# 20_CLOCKS.net
KiCad netlist of a schematic drawn in Altium Designer
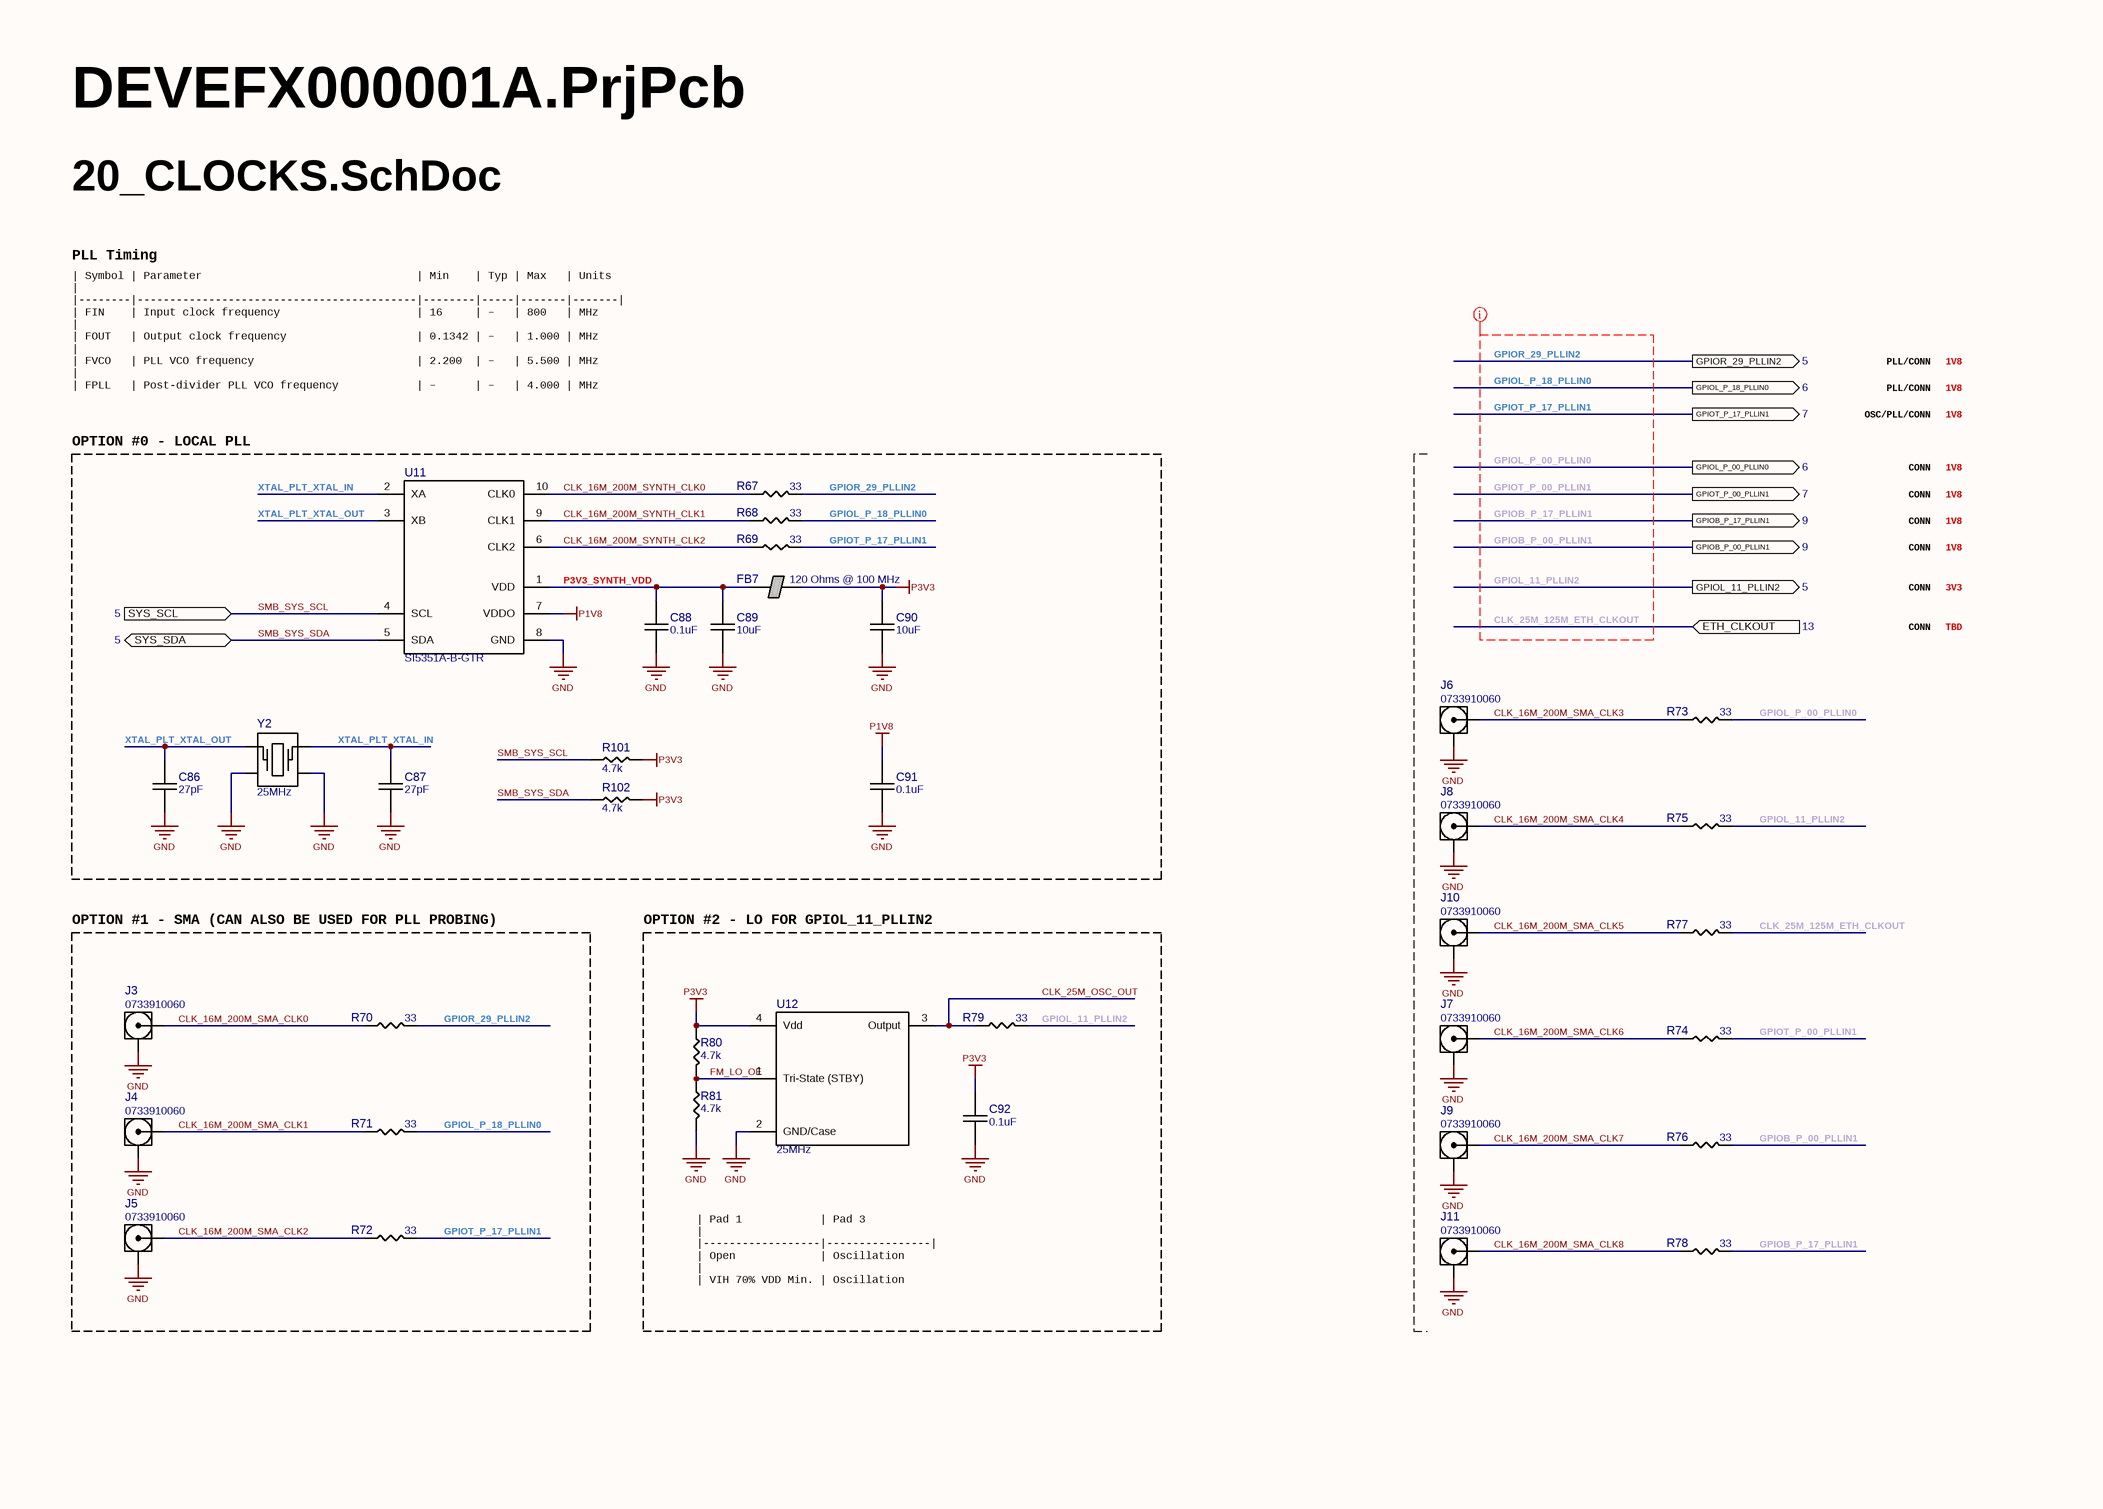
[diagram p0: 20_CLOCKS.SchDoc]

(export (version "E")
  (design (tool "Eeschema 10.0.6"))
  (components
    (comp (ref "C86")
      (value "27pF")
      (footprint "CAPC1005X06N")
      (description "CAP CER 27PF 50V C0G/NPO 0402")
      (fields (field (name "PART NUMBER") "CC0402JRNPO9BN270") (field (name "VOLTAGE") "50V"))
      (libsource (lib "Database") (part "Capacitor"))
    )
    (comp (ref "C87")
      (value "27pF")
      (footprint "CAPC1005X06N")
      (description "CAP CER 27PF 50V C0G/NPO 0402")
      (fields (field (name "PART NUMBER") "CC0402JRNPO9BN270") (field (name "VOLTAGE") "50V"))
      (libsource (lib "Database") (part "Capacitor"))
    )
    (comp (ref "C88")
      (value "0.1uF")
      (footprint "CAPC1005X06N")
      (description "CAP CER 0.1UF 25V X7R 0402")
      (fields (field (name "PART NUMBER") "GRM155R71E104KE14J") (field (name "VOLTAGE") "25V"))
      (libsource (lib "Database") (part "Capacitor"))
    )
    (comp (ref "C89")
      (value "10uF")
      (footprint "CAPC1005X06N")
      (description "CAP CER 10UF 6.3V X5R 0402")
      (fields (field (name "PART NUMBER") "GRM155R60J106ME47D") (field (name "VOLTAGE") "6.3V"))
      (libsource (lib "Database") (part "Capacitor"))
    )
    (comp (ref "C90")
      (value "10uF")
      (footprint "CAPC1005X06N")
      (description "CAP CER 10UF 6.3V X5R 0402")
      (fields (field (name "PART NUMBER") "GRM155R60J106ME47D") (field (name "VOLTAGE") "6.3V"))
      (libsource (lib "Database") (part "Capacitor"))
    )
    (comp (ref "C91")
      (value "0.1uF")
      (footprint "CAPC1005X06N")
      (description "CAP CER 0.1UF 25V X7R 0402")
      (fields (field (name "PART NUMBER") "GRM155R71E104KE14J") (field (name "VOLTAGE") "25V"))
      (libsource (lib "Database") (part "Capacitor"))
    )
    (comp (ref "C92")
      (value "0.1uF")
      (footprint "CAPC1005X06N")
      (description "CAP CER 0.1UF 25V X7R 0402")
      (fields (field (name "PART NUMBER") "GRM155R71E104KE14J") (field (name "VOLTAGE") "25V"))
      (libsource (lib "Database") (part "Capacitor"))
    )
    (comp (ref "FB7")
      (value "120 Ohms @ 100 MHz")
      (footprint "INDC1005X05N")
      (description "FERRITE BEAD 120 OHM 0402 1LN")
      (fields (field (name "PART NUMBER") "BLM15PD121SN1D"))
      (libsource (lib "Database") (part "Bead"))
    )
    (comp (ref "J3")
      (value "0733910060")
      (footprint "MOLEX_0733910060")
      (description "CONN SMA RCPT STR 50 OHM PCB")
      (libsource (lib "Database") (part "Connector RF"))
    )
    (comp (ref "J4")
      (value "0733910060")
      (footprint "MOLEX_0733910060")
      (description "CONN SMA RCPT STR 50 OHM PCB")
      (libsource (lib "Database") (part "Connector RF"))
    )
    (comp (ref "J5")
      (value "0733910060")
      (footprint "MOLEX_0733910060")
      (description "CONN SMA RCPT STR 50 OHM PCB")
      (libsource (lib "Database") (part "Connector RF"))
    )
    (comp (ref "J6")
      (value "0733910060")
      (footprint "MOLEX_0733910060")
      (description "CONN SMA RCPT STR 50 OHM PCB")
      (libsource (lib "Database") (part "Connector RF"))
    )
    (comp (ref "J7")
      (value "0733910060")
      (footprint "MOLEX_0733910060")
      (description "CONN SMA RCPT STR 50 OHM PCB")
      (libsource (lib "Database") (part "Connector RF"))
    )
    (comp (ref "J8")
      (value "0733910060")
      (footprint "MOLEX_0733910060")
      (description "CONN SMA RCPT STR 50 OHM PCB")
      (libsource (lib "Database") (part "Connector RF"))
    )
    (comp (ref "J9")
      (value "0733910060")
      (footprint "MOLEX_0733910060")
      (description "CONN SMA RCPT STR 50 OHM PCB")
      (libsource (lib "Database") (part "Connector RF"))
    )
    (comp (ref "J10")
      (value "0733910060")
      (footprint "MOLEX_0733910060")
      (description "CONN SMA RCPT STR 50 OHM PCB")
      (libsource (lib "Database") (part "Connector RF"))
    )
    (comp (ref "J11")
      (value "0733910060")
      (footprint "MOLEX_0733910060")
      (description "CONN SMA RCPT STR 50 OHM PCB")
      (libsource (lib "Database") (part "Connector RF"))
    )
    (comp (ref "R67")
      (value "33")
      (footprint "RESC1005X03N")
      (description "RES SMD 33 OHM 1% 1/16W 0402")
      (fields (field (name "PART NUMBER") "RC0402FR-0733RL"))
      (libsource (lib "Database") (part "Resistor_ENG"))
    )
    (comp (ref "R68")
      (value "33")
      (footprint "RESC1005X03N")
      (description "RES SMD 33 OHM 1% 1/16W 0402")
      (fields (field (name "PART NUMBER") "RC0402FR-0733RL"))
      (libsource (lib "Database") (part "Resistor_ENG"))
    )
    (comp (ref "R69")
      (value "33")
      (footprint "RESC1005X03N")
      (description "RES SMD 33 OHM 1% 1/16W 0402")
      (fields (field (name "PART NUMBER") "RC0402FR-0733RL"))
      (libsource (lib "Database") (part "Resistor_ENG"))
    )
    (comp (ref "R70")
      (value "33")
      (footprint "RESC1005X03N")
      (description "RES SMD 33 OHM 1% 1/16W 0402")
      (fields (field (name "PART NUMBER") "RC0402FR-0733RL"))
      (libsource (lib "Database") (part "Resistor_ENG"))
    )
    (comp (ref "R71")
      (value "33")
      (footprint "RESC1005X03N")
      (description "RES SMD 33 OHM 1% 1/16W 0402")
      (fields (field (name "PART NUMBER") "RC0402FR-0733RL"))
      (libsource (lib "Database") (part "Resistor_ENG"))
    )
    (comp (ref "R72")
      (value "33")
      (footprint "RESC1005X03N")
      (description "RES SMD 33 OHM 1% 1/16W 0402")
      (fields (field (name "PART NUMBER") "RC0402FR-0733RL"))
      (libsource (lib "Database") (part "Resistor_ENG"))
    )
    (comp (ref "R73")
      (value "33")
      (footprint "RESC1005X03N")
      (description "RES SMD 33 OHM 1% 1/16W 0402")
      (fields (field (name "PART NUMBER") "RC0402FR-0733RL"))
      (libsource (lib "Database") (part "Resistor_ENG"))
    )
    (comp (ref "R74")
      (value "33")
      (footprint "RESC1005X03N")
      (description "RES SMD 33 OHM 1% 1/16W 0402")
      (fields (field (name "PART NUMBER") "RC0402FR-0733RL"))
      (libsource (lib "Database") (part "Resistor_ENG"))
    )
    (comp (ref "R75")
      (value "33")
      (footprint "RESC1005X03N")
      (description "RES SMD 33 OHM 1% 1/16W 0402")
      (fields (field (name "PART NUMBER") "RC0402FR-0733RL"))
      (libsource (lib "Database") (part "Resistor_ENG"))
    )
    (comp (ref "R76")
      (value "33")
      (footprint "RESC1005X03N")
      (description "RES SMD 33 OHM 1% 1/16W 0402")
      (fields (field (name "PART NUMBER") "RC0402FR-0733RL"))
      (libsource (lib "Database") (part "Resistor_ENG"))
    )
    (comp (ref "R77")
      (value "33")
      (footprint "RESC1005X03N")
      (description "RES SMD 33 OHM 1% 1/16W 0402")
      (fields (field (name "PART NUMBER") "RC0402FR-0733RL"))
      (libsource (lib "Database") (part "Resistor_ENG"))
    )
    (comp (ref "R78")
      (value "33")
      (footprint "RESC1005X03N")
      (description "RES SMD 33 OHM 1% 1/16W 0402")
      (fields (field (name "PART NUMBER") "RC0402FR-0733RL"))
      (libsource (lib "Database") (part "Resistor_ENG"))
    )
    (comp (ref "R79")
      (value "33")
      (footprint "RESC1005X03N")
      (description "RES SMD 33 OHM 1% 1/16W 0402")
      (fields (field (name "PART NUMBER") "RC0402FR-0733RL"))
      (libsource (lib "Database") (part "Resistor_ENG"))
    )
    (comp (ref "R80")
      (value "4.7k")
      (footprint "RESC1005X03N")
      (description "RES SMD 4.7K OHM 1% 1/16W 0402")
      (fields (field (name "PART NUMBER") "RC0402FR-074K7L"))
      (libsource (lib "Database") (part "Resistor_ENG"))
    )
    (comp (ref "R81")
      (value "4.7k")
      (footprint "RESC1005X03N")
      (description "RES SMD 4.7K OHM 1% 1/16W 0402")
      (fields (field (name "PART NUMBER") "RC0402FR-074K7L"))
      (libsource (lib "Database") (part "Resistor_ENG"))
    )
    (comp (ref "R101")
      (value "4.7k")
      (footprint "RESC1005X03N")
      (description "RES SMD 4.7K OHM 1% 1/16W 0402")
      (fields (field (name "PART NUMBER") "RC0402FR-074K7L"))
      (libsource (lib "Database") (part "Resistor_ENG"))
    )
    (comp (ref "R102")
      (value "4.7k")
      (footprint "RESC1005X03N")
      (description "RES SMD 4.7K OHM 1% 1/16W 0402")
      (fields (field (name "PART NUMBER") "RC0402FR-074K7L"))
      (libsource (lib "Database") (part "Resistor_ENG"))
    )
    (comp (ref "U11")
      (value "SI5351A-B-GTR")
      (footprint "TSSOP50P490X110-10N")
      (description "IC CLK GENERATOR 200MHZ 10MSOP")
      (libsource (lib "Database") (part "Si5351_GT"))
    )
    (comp (ref "U12")
      (value "25MHz")
      (footprint "XTAL_2520")
      (description "XTAL OSC XO 25.0000MHZ CMOS SMD")
      (fields (field (name "PART NUMBER") "ECS-2033-250-BN"))
      (libsource (lib "Database") (part "Oscillator 4T"))
    )
    (comp (ref "Y2")
      (value "25MHz")
      (footprint "XTAL_3225")
      (description "CRYSTAL 25.0000MHZ 18PF SMD")
      (fields (field (name "PART NUMBER") "TSX-3225 25.0000MF10P-C0"))
      (libsource (lib "Database") (part "Crystal_1"))
    )
  )
  (nets
    (net (code "1") (name "/CLK_16M_200M_SMA_CLK0") (class "Default")
      (node (ref "J3") (pin "1") (pinfunction "1_1") (pintype "passive"))
      (node (ref "R70") (pin "1") (pinfunction "1_1") (pintype "passive"))
    )
    (net (code "2") (name "/CLK_16M_200M_SMA_CLK1") (class "Default")
      (node (ref "J4") (pin "1") (pinfunction "1_1") (pintype "passive"))
      (node (ref "R71") (pin "1") (pinfunction "1_1") (pintype "passive"))
    )
    (net (code "3") (name "/CLK_16M_200M_SMA_CLK2") (class "Default")
      (node (ref "J5") (pin "1") (pinfunction "1_1") (pintype "passive"))
      (node (ref "R72") (pin "1") (pinfunction "1_1") (pintype "passive"))
    )
    (net (code "4") (name "/CLK_16M_200M_SMA_CLK3") (class "Default")
      (node (ref "J6") (pin "1") (pinfunction "1_1") (pintype "passive"))
      (node (ref "R73") (pin "1") (pinfunction "1_1") (pintype "passive"))
    )
    (net (code "5") (name "/CLK_16M_200M_SMA_CLK4") (class "Default")
      (node (ref "J8") (pin "1") (pinfunction "1_1") (pintype "passive"))
      (node (ref "R75") (pin "1") (pinfunction "1_1") (pintype "passive"))
    )
    (net (code "6") (name "/CLK_16M_200M_SMA_CLK5") (class "Default")
      (node (ref "J10") (pin "1") (pinfunction "1_1") (pintype "passive"))
      (node (ref "R77") (pin "1") (pinfunction "1_1") (pintype "passive"))
    )
    (net (code "7") (name "/CLK_16M_200M_SMA_CLK6") (class "Default")
      (node (ref "J7") (pin "1") (pinfunction "1_1") (pintype "passive"))
      (node (ref "R74") (pin "1") (pinfunction "1_1") (pintype "passive"))
    )
    (net (code "8") (name "/CLK_16M_200M_SMA_CLK7") (class "Default")
      (node (ref "J9") (pin "1") (pinfunction "1_1") (pintype "passive"))
      (node (ref "R76") (pin "1") (pinfunction "1_1") (pintype "passive"))
    )
    (net (code "9") (name "/CLK_16M_200M_SMA_CLK8") (class "Default")
      (node (ref "J11") (pin "1") (pinfunction "1_1") (pintype "passive"))
      (node (ref "R78") (pin "1") (pinfunction "1_1") (pintype "passive"))
    )
    (net (code "10") (name "/CLK_16M_200M_SYNTH_CLK0") (class "Default")
      (node (ref "R67") (pin "1") (pinfunction "1_1") (pintype "passive"))
      (node (ref "U11") (pin "10") (pinfunction "CLK0_10") (pintype "passive"))
    )
    (net (code "11") (name "/CLK_16M_200M_SYNTH_CLK1") (class "Default")
      (node (ref "R68") (pin "1") (pinfunction "1_1") (pintype "passive"))
      (node (ref "U11") (pin "9") (pinfunction "CLK1_9") (pintype "passive"))
    )
    (net (code "12") (name "/CLK_16M_200M_SYNTH_CLK2") (class "Default")
      (node (ref "R69") (pin "1") (pinfunction "1_1") (pintype "passive"))
      (node (ref "U11") (pin "6") (pinfunction "CLK2_6") (pintype "passive"))
    )
    (net (code "13") (name "/CLK_25M_125M_ETH_CLKOUT") (class "Default")
      (node (ref "R77") (pin "2") (pinfunction "2_2") (pintype "passive"))
    )
    (net (code "14") (name "/CLK_25M_OSC_OUT") (class "Default")
      (node (ref "R79") (pin "1") (pinfunction "1_1") (pintype "passive"))
      (node (ref "U12") (pin "3") (pinfunction "Output_3") (pintype "passive"))
    )
    (net (code "15") (name "/FM_LO_OE") (class "Default")
      (node (ref "R80") (pin "2") (pinfunction "2_2") (pintype "passive"))
      (node (ref "R81") (pin "1") (pinfunction "1_1") (pintype "passive"))
      (node (ref "U12") (pin "1") (pinfunction "Tri-State_(STBY)_1") (pintype "passive"))
    )
    (net (code "16") (name "/GPIOB_P_00_PLLIN1") (class "Default")
      (node (ref "R76") (pin "2") (pinfunction "2_2") (pintype "passive"))
    )
    (net (code "17") (name "/GPIOB_P_17_PLLIN1") (class "Default")
      (node (ref "R78") (pin "2") (pinfunction "2_2") (pintype "passive"))
    )
    (net (code "18") (name "/GPIOL_11_PLLIN2") (class "Default")
      (node (ref "R75") (pin "2") (pinfunction "2_2") (pintype "passive"))
      (node (ref "R79") (pin "2") (pinfunction "2_2") (pintype "passive"))
    )
    (net (code "19") (name "/GPIOL_P_00_PLLIN0") (class "Default")
      (node (ref "R73") (pin "2") (pinfunction "2_2") (pintype "passive"))
    )
    (net (code "20") (name "/GPIOL_P_18_PLLIN0") (class "Default")
      (node (ref "R68") (pin "2") (pinfunction "2_2") (pintype "passive"))
      (node (ref "R71") (pin "2") (pinfunction "2_2") (pintype "passive"))
    )
    (net (code "21") (name "/GPIOR_29_PLLIN2") (class "Default")
      (node (ref "R67") (pin "2") (pinfunction "2_2") (pintype "passive"))
      (node (ref "R70") (pin "2") (pinfunction "2_2") (pintype "passive"))
    )
    (net (code "22") (name "/GPIOT_P_00_PLLIN1") (class "Default")
      (node (ref "R74") (pin "2") (pinfunction "2_2") (pintype "passive"))
    )
    (net (code "23") (name "/GPIOT_P_17_PLLIN1") (class "Default")
      (node (ref "R69") (pin "2") (pinfunction "2_2") (pintype "passive"))
      (node (ref "R72") (pin "2") (pinfunction "2_2") (pintype "passive"))
    )
    (net (code "24") (name "/P3V3_SYNTH_VDD") (class "Default")
      (node (ref "C88") (pin "2") (pinfunction "2_2") (pintype "passive"))
      (node (ref "C89") (pin "2") (pinfunction "2_2") (pintype "passive"))
      (node (ref "FB7") (pin "1") (pinfunction "1_1") (pintype "passive"))
      (node (ref "U11") (pin "1") (pinfunction "VDD_1") (pintype "passive"))
    )
    (net (code "25") (name "/SMB_SYS_SCL") (class "Default")
      (node (ref "R101") (pin "1") (pinfunction "1_1") (pintype "passive"))
      (node (ref "U11") (pin "4") (pinfunction "SCL_4") (pintype "passive"))
    )
    (net (code "26") (name "/SMB_SYS_SDA") (class "Default")
      (node (ref "R102") (pin "1") (pinfunction "1_1") (pintype "passive"))
      (node (ref "U11") (pin "5") (pinfunction "SDA_5") (pintype "passive"))
    )
    (net (code "27") (name "/XTAL_PLT_XTAL_IN") (class "Default")
      (node (ref "C87") (pin "2") (pinfunction "2_2") (pintype "passive"))
      (node (ref "U11") (pin "2") (pinfunction "XA_2") (pintype "passive"))
      (node (ref "Y2") (pin "3") (pinfunction "3_3") (pintype "passive"))
    )
    (net (code "28") (name "/XTAL_PLT_XTAL_OUT") (class "Default")
      (node (ref "C86") (pin "2") (pinfunction "2_2") (pintype "passive"))
      (node (ref "U11") (pin "3") (pinfunction "XB_3") (pintype "passive"))
      (node (ref "Y2") (pin "1") (pinfunction "1_1") (pintype "passive"))
    )
    (net (code "29") (name "GND") (class "Default")
      (node (ref "C86") (pin "1") (pinfunction "1_1") (pintype "passive"))
      (node (ref "C87") (pin "1") (pinfunction "1_1") (pintype "passive"))
      (node (ref "C88") (pin "1") (pinfunction "1_1") (pintype "passive"))
      (node (ref "C89") (pin "1") (pinfunction "1_1") (pintype "passive"))
      (node (ref "C90") (pin "1") (pinfunction "1_1") (pintype "passive"))
      (node (ref "C91") (pin "1") (pinfunction "1_1") (pintype "passive"))
      (node (ref "C92") (pin "1") (pinfunction "1_1") (pintype "passive"))
      (node (ref "J10") (pin "2") (pinfunction "2_2") (pintype "passive"))
      (node (ref "J11") (pin "2") (pinfunction "2_2") (pintype "passive"))
      (node (ref "J3") (pin "2") (pinfunction "2_2") (pintype "passive"))
      (node (ref "J4") (pin "2") (pinfunction "2_2") (pintype "passive"))
      (node (ref "J5") (pin "2") (pinfunction "2_2") (pintype "passive"))
      (node (ref "J6") (pin "2") (pinfunction "2_2") (pintype "passive"))
      (node (ref "J7") (pin "2") (pinfunction "2_2") (pintype "passive"))
      (node (ref "J8") (pin "2") (pinfunction "2_2") (pintype "passive"))
      (node (ref "J9") (pin "2") (pinfunction "2_2") (pintype "passive"))
      (node (ref "R81") (pin "2") (pinfunction "2_2") (pintype "passive"))
      (node (ref "U11") (pin "8") (pinfunction "GND_8") (pintype "passive"))
      (node (ref "U12") (pin "2") (pinfunction "GND/Case_2") (pintype "passive"))
      (node (ref "Y2") (pin "2") (pinfunction "2_2") (pintype "passive"))
      (node (ref "Y2") (pin "4") (pinfunction "4_4") (pintype "passive"))
    )
    (net (code "30") (name "P1V8") (class "Default")
      (node (ref "C91") (pin "2") (pinfunction "2_2") (pintype "passive"))
      (node (ref "U11") (pin "7") (pinfunction "VDDO_7") (pintype "passive"))
    )
    (net (code "31") (name "P3V3") (class "Default")
      (node (ref "C90") (pin "2") (pinfunction "2_2") (pintype "passive"))
      (node (ref "C92") (pin "2") (pinfunction "2_2") (pintype "passive"))
      (node (ref "FB7") (pin "2") (pinfunction "2_2") (pintype "passive"))
      (node (ref "R101") (pin "2") (pinfunction "2_2") (pintype "passive"))
      (node (ref "R102") (pin "2") (pinfunction "2_2") (pintype "passive"))
      (node (ref "R80") (pin "1") (pinfunction "1_1") (pintype "passive"))
      (node (ref "U12") (pin "4") (pinfunction "Vdd_4") (pintype "passive"))
    )
  )
)
